# LoRaBee.net
KiCad netlist of a schematic drawn in EAGLE
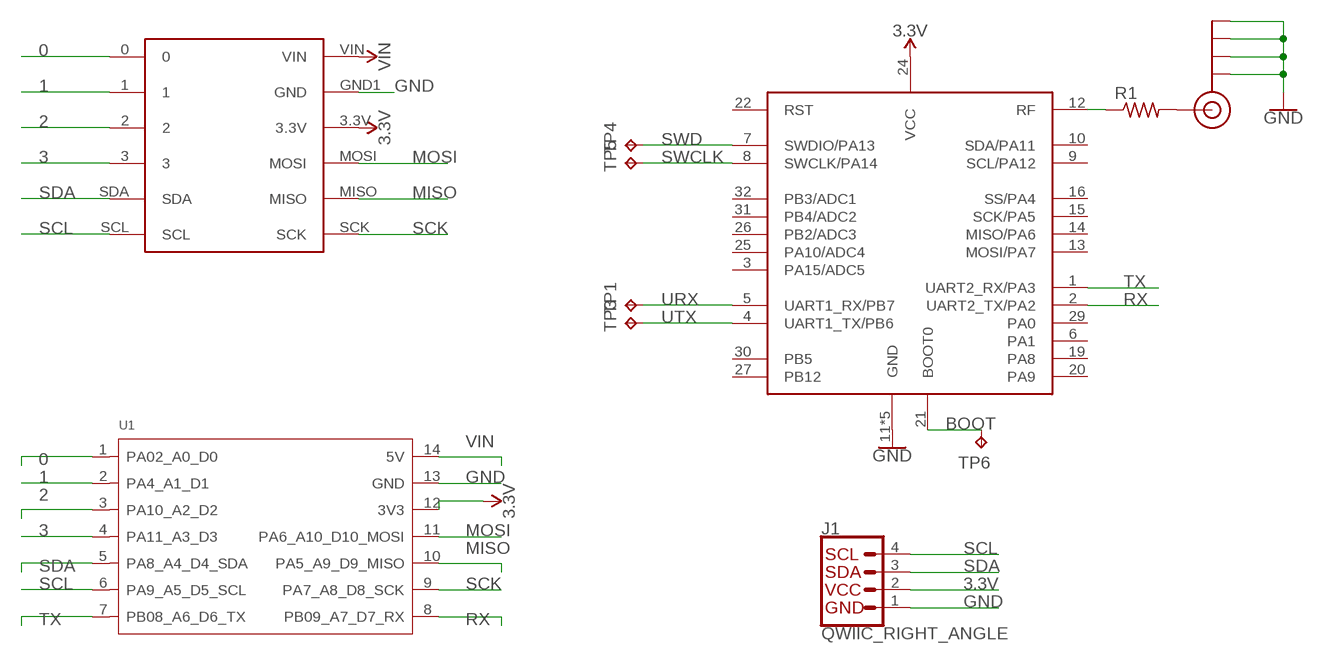
[diagram p0: schematic, sheet 1]

(export (version "E")
  (design (tool "Eeschema 10.0.6"))
  (components
    (comp (ref "J$1")
      (value "SMA_EDGE")
      (footprint "eagle-import:SMA-EDGE")
      (libsource (lib "eagle-import") (part "SMA_EDGE"))
    )
    (comp (ref "J1")
      (value "QWIIC_RIGHT_ANGLE")
      (footprint "eagle-import:JST04_1MM_RA")
      (libsource (lib "eagle-import") (part "QWIIC_CONNECTORJS-1MM"))
    )
    (comp (ref "R1")
      (value "R-US_R0805")
      (footprint "eagle-import:R0805")
      (libsource (lib "eagle-import") (part "R-US_R0805"))
    )
    (comp (ref "TP1")
      (value "TPTP12R")
      (footprint "eagle-import:TP12R")
      (libsource (lib "eagle-import") (part "TPTP12R"))
    )
    (comp (ref "TP3")
      (value "TPTP12R")
      (footprint "eagle-import:TP12R")
      (libsource (lib "eagle-import") (part "TPTP12R"))
    )
    (comp (ref "TP4")
      (value "TPTP12R")
      (footprint "eagle-import:TP12R")
      (libsource (lib "eagle-import") (part "TPTP12R"))
    )
    (comp (ref "TP5")
      (value "TPTP12R")
      (footprint "eagle-import:TP12R")
      (libsource (lib "eagle-import") (part "TPTP12R"))
    )
    (comp (ref "TP6")
      (value "TPTP12R")
      (footprint "eagle-import:TP12R")
      (libsource (lib "eagle-import") (part "TPTP12R"))
    )
    (comp (ref "U$1")
      (value "BEEELINK")
      (footprint "eagle-import:BEEELINK")
      (libsource (lib "eagle-import") (part "BEEELINK"))
    )
    (comp (ref "U$2")
      (value "RAK3172HF")
      (footprint "eagle-import:RAK3172")
      (libsource (lib "eagle-import") (part "RAK3172HF"))
    )
    (comp (ref "U1")
      (value "MOUDLE-SEEEDUINO-XIAO")
      (footprint "eagle-import:MOUDLE14P-2.54-21X17.8MM")
      (libsource (lib "eagle-import") (part "MOUDLE-SEEEDUINO-XIAO"))
    )
  )
  (nets
    (net (code "1") (name "/0") (class "Default")
      (node (ref "U$1") (pin "0") (pinfunction "0_0") (pintype "bidirectional"))
      (node (ref "U1") (pin "1") (pinfunction "PA02_A0_D0_1") (pintype "bidirectional"))
    )
    (net (code "2") (name "/1") (class "Default")
      (node (ref "U$1") (pin "1") (pinfunction "1_1") (pintype "bidirectional"))
      (node (ref "U1") (pin "2") (pinfunction "PA4_A1_D1_2") (pintype "bidirectional"))
    )
    (net (code "3") (name "/2") (class "Default")
      (node (ref "U$1") (pin "2") (pinfunction "2_2") (pintype "bidirectional"))
      (node (ref "U1") (pin "3") (pinfunction "PA10_A2_D2_3") (pintype "bidirectional"))
    )
    (net (code "4") (name "/3") (class "Default")
      (node (ref "U$1") (pin "3") (pinfunction "3_3") (pintype "bidirectional"))
      (node (ref "U1") (pin "4") (pinfunction "PA11_A3_D3_4") (pintype "bidirectional"))
    )
    (net (code "5") (name "/BOOT") (class "Default")
      (node (ref "TP6") (pin "TP") (pinfunction "TP_TP") (pintype "input"))
      (node (ref "U$2") (pin "21") (pinfunction "BOOT0_21") (pintype "input"))
    )
    (net (code "6") (name "/MISO") (class "Default")
      (node (ref "U$1") (pin "MISO") (pinfunction "MISO_MISO") (pintype "bidirectional"))
      (node (ref "U1") (pin "10") (pinfunction "PA5_A9_D9_MISO_10") (pintype "bidirectional"))
    )
    (net (code "7") (name "/MOSI") (class "Default")
      (node (ref "U$1") (pin "MOSI") (pinfunction "MOSI_MOSI") (pintype "bidirectional"))
      (node (ref "U1") (pin "11") (pinfunction "PA6_A10_D10_MOSI_11") (pintype "bidirectional"))
    )
    (net (code "8") (name "/RX") (class "Default")
      (node (ref "U$2") (pin "2") (pinfunction "UART2_TX/PA2_2") (pintype "bidirectional"))
      (node (ref "U1") (pin "8") (pinfunction "PB09_A7_D7_RX_8") (pintype "bidirectional"))
    )
    (net (code "9") (name "/SCK") (class "Default")
      (node (ref "U$1") (pin "SCK") (pinfunction "SCK_SCK") (pintype "bidirectional"))
      (node (ref "U1") (pin "9") (pinfunction "PA7_A8_D8_SCK_9") (pintype "bidirectional"))
    )
    (net (code "10") (name "/SCL") (class "Default")
      (node (ref "J1") (pin "4") (pinfunction "4_4") (pintype "passive"))
      (node (ref "U$1") (pin "SCL") (pinfunction "SCL_SCL") (pintype "bidirectional"))
      (node (ref "U1") (pin "6") (pinfunction "PA9_A5_D5_SCL_6") (pintype "bidirectional"))
    )
    (net (code "11") (name "/SDA") (class "Default")
      (node (ref "J1") (pin "3") (pinfunction "3_3") (pintype "passive"))
      (node (ref "U$1") (pin "SDA") (pinfunction "SDA_SDA") (pintype "bidirectional"))
      (node (ref "U1") (pin "5") (pinfunction "PA8_A4_D4_SDA_5") (pintype "bidirectional"))
    )
    (net (code "12") (name "/SWCLK") (class "Default")
      (node (ref "TP5") (pin "TP") (pinfunction "TP_TP") (pintype "input"))
      (node (ref "U$2") (pin "8") (pinfunction "SWCLK/PA14_8") (pintype "bidirectional"))
    )
    (net (code "13") (name "/SWD") (class "Default")
      (node (ref "TP4") (pin "TP") (pinfunction "TP_TP") (pintype "input"))
      (node (ref "U$2") (pin "7") (pinfunction "SWDIO/PA13_7") (pintype "bidirectional"))
    )
    (net (code "14") (name "/TX") (class "Default")
      (node (ref "U$2") (pin "1") (pinfunction "UART2_RX/PA3_1") (pintype "bidirectional"))
      (node (ref "U1") (pin "7") (pinfunction "PB08_A6_D6_TX_7") (pintype "bidirectional"))
    )
    (net (code "15") (name "/URX") (class "Default")
      (node (ref "TP1") (pin "TP") (pinfunction "TP_TP") (pintype "input"))
      (node (ref "U$2") (pin "5") (pinfunction "UART1_RX/PB7_5") (pintype "bidirectional"))
    )
    (net (code "16") (name "/UTX") (class "Default")
      (node (ref "TP3") (pin "TP") (pinfunction "TP_TP") (pintype "input"))
      (node (ref "U$2") (pin "4") (pinfunction "UART1_TX/PB6_4") (pintype "bidirectional"))
    )
    (net (code "17") (name "3.3V") (class "Default")
      (node (ref "J1") (pin "2") (pinfunction "2_2") (pintype "power_in"))
      (node (ref "U$1") (pin "3.3V") (pinfunction "3.3V_3.3V") (pintype "bidirectional"))
      (node (ref "U$2") (pin "24") (pinfunction "VCC_24") (pintype "power_in"))
      (node (ref "U1") (pin "12") (pinfunction "3V3_12") (pintype "bidirectional"))
    )
    (net (code "18") (name "GND") (class "Default")
      (node (ref "J$1") (pin "GND@0") (pinfunction "GND_GND@0") (pintype "bidirectional"))
      (node (ref "J$1") (pin "GND@1") (pinfunction "GND_GND@1") (pintype "bidirectional"))
      (node (ref "J$1") (pin "GND@2") (pinfunction "GND_GND@2") (pintype "bidirectional"))
      (node (ref "J$1") (pin "GND@3") (pinfunction "GND_GND@3") (pintype "bidirectional"))
      (node (ref "J1") (pin "1") (pinfunction "1_1") (pintype "power_in"))
      (node (ref "U$1") (pin "GND1") (pinfunction "GND_GND1") (pintype "bidirectional"))
      (node (ref "U$2") (pin "11") (pinfunction "GND_11") (pintype "power_in"))
      (node (ref "U$2") (pin "17") (pinfunction "GND_17") (pintype "power_in"))
      (node (ref "U$2") (pin "18") (pinfunction "GND_18") (pintype "power_in"))
      (node (ref "U$2") (pin "23") (pinfunction "GND_23") (pintype "power_in"))
      (node (ref "U$2") (pin "28") (pinfunction "GND_28") (pintype "power_in"))
      (node (ref "U1") (pin "13") (pinfunction "GND_13") (pintype "bidirectional"))
    )
    (net (code "19") (name "Net-(J$1-SIGNAL)") (class "Default")
      (node (ref "J$1") (pin "SIG") (pinfunction "SIGNAL_SIG") (pintype "bidirectional"))
      (node (ref "R1") (pin "2") (pinfunction "2_2") (pintype "passive"))
    )
    (net (code "20") (name "Net-(U$2-RF)") (class "Default")
      (node (ref "R1") (pin "1") (pinfunction "1_1") (pintype "passive"))
      (node (ref "U$2") (pin "12") (pinfunction "RF_12") (pintype "output"))
    )
    (net (code "21") (name "VIN") (class "Default")
      (node (ref "U$1") (pin "VIN") (pinfunction "VIN_VIN") (pintype "bidirectional"))
      (node (ref "U1") (pin "14") (pinfunction "5V_14") (pintype "bidirectional"))
    )
    (net (code "22") (name "unconnected-(U$2-MISO{slash}PA6-Pad14)") (class "Default")
      (node (ref "U$2") (pin "14") (pinfunction "MISO/PA6_14") (pintype "bidirectional"))
    )
    (net (code "23") (name "unconnected-(U$2-MOSI{slash}PA7-Pad13)") (class "Default")
      (node (ref "U$2") (pin "13") (pinfunction "MOSI/PA7_13") (pintype "bidirectional"))
    )
    (net (code "24") (name "unconnected-(U$2-PA0-Pad29)") (class "Default")
      (node (ref "U$2") (pin "29") (pinfunction "PA0_29") (pintype "bidirectional"))
    )
    (net (code "25") (name "unconnected-(U$2-PA1-Pad6)") (class "Default")
      (node (ref "U$2") (pin "6") (pinfunction "PA1_6") (pintype "bidirectional"))
    )
    (net (code "26") (name "unconnected-(U$2-PA8-Pad19)") (class "Default")
      (node (ref "U$2") (pin "19") (pinfunction "PA8_19") (pintype "bidirectional"))
    )
    (net (code "27") (name "unconnected-(U$2-PA9-Pad20)") (class "Default")
      (node (ref "U$2") (pin "20") (pinfunction "PA9_20") (pintype "bidirectional"))
    )
    (net (code "28") (name "unconnected-(U$2-PA10{slash}ADC4-Pad25)") (class "Default")
      (node (ref "U$2") (pin "25") (pinfunction "PA10/ADC4_25") (pintype "bidirectional"))
    )
    (net (code "29") (name "unconnected-(U$2-PA15{slash}ADC5-Pad3)") (class "Default")
      (node (ref "U$2") (pin "3") (pinfunction "PA15/ADC5_3") (pintype "bidirectional"))
    )
    (net (code "30") (name "unconnected-(U$2-PB2{slash}ADC3-Pad26)") (class "Default")
      (node (ref "U$2") (pin "26") (pinfunction "PB2/ADC3_26") (pintype "bidirectional"))
    )
    (net (code "31") (name "unconnected-(U$2-PB3{slash}ADC1-Pad32)") (class "Default")
      (node (ref "U$2") (pin "32") (pinfunction "PB3/ADC1_32") (pintype "bidirectional"))
    )
    (net (code "32") (name "unconnected-(U$2-PB4{slash}ADC2-Pad31)") (class "Default")
      (node (ref "U$2") (pin "31") (pinfunction "PB4/ADC2_31") (pintype "bidirectional"))
    )
    (net (code "33") (name "unconnected-(U$2-PB5-Pad30)") (class "Default")
      (node (ref "U$2") (pin "30") (pinfunction "PB5_30") (pintype "bidirectional"))
    )
    (net (code "34") (name "unconnected-(U$2-PB12-Pad27)") (class "Default")
      (node (ref "U$2") (pin "27") (pinfunction "PB12_27") (pintype "bidirectional"))
    )
    (net (code "35") (name "unconnected-(U$2-RST-Pad22)") (class "Default")
      (node (ref "U$2") (pin "22") (pinfunction "RST_22") (pintype "input"))
    )
    (net (code "36") (name "unconnected-(U$2-SCK{slash}PA5-Pad15)") (class "Default")
      (node (ref "U$2") (pin "15") (pinfunction "SCK/PA5_15") (pintype "bidirectional"))
    )
    (net (code "37") (name "unconnected-(U$2-SCL{slash}PA12-Pad9)") (class "Default")
      (node (ref "U$2") (pin "9") (pinfunction "SCL/PA12_9") (pintype "bidirectional"))
    )
    (net (code "38") (name "unconnected-(U$2-SDA{slash}PA11-Pad10)") (class "Default")
      (node (ref "U$2") (pin "10") (pinfunction "SDA/PA11_10") (pintype "bidirectional"))
    )
    (net (code "39") (name "unconnected-(U$2-SS{slash}PA4-Pad16)") (class "Default")
      (node (ref "U$2") (pin "16") (pinfunction "SS/PA4_16") (pintype "bidirectional"))
    )
  )
)
